# Buck_Boost_19V.net
KiCad netlist of a schematic drawn in Altium Designer
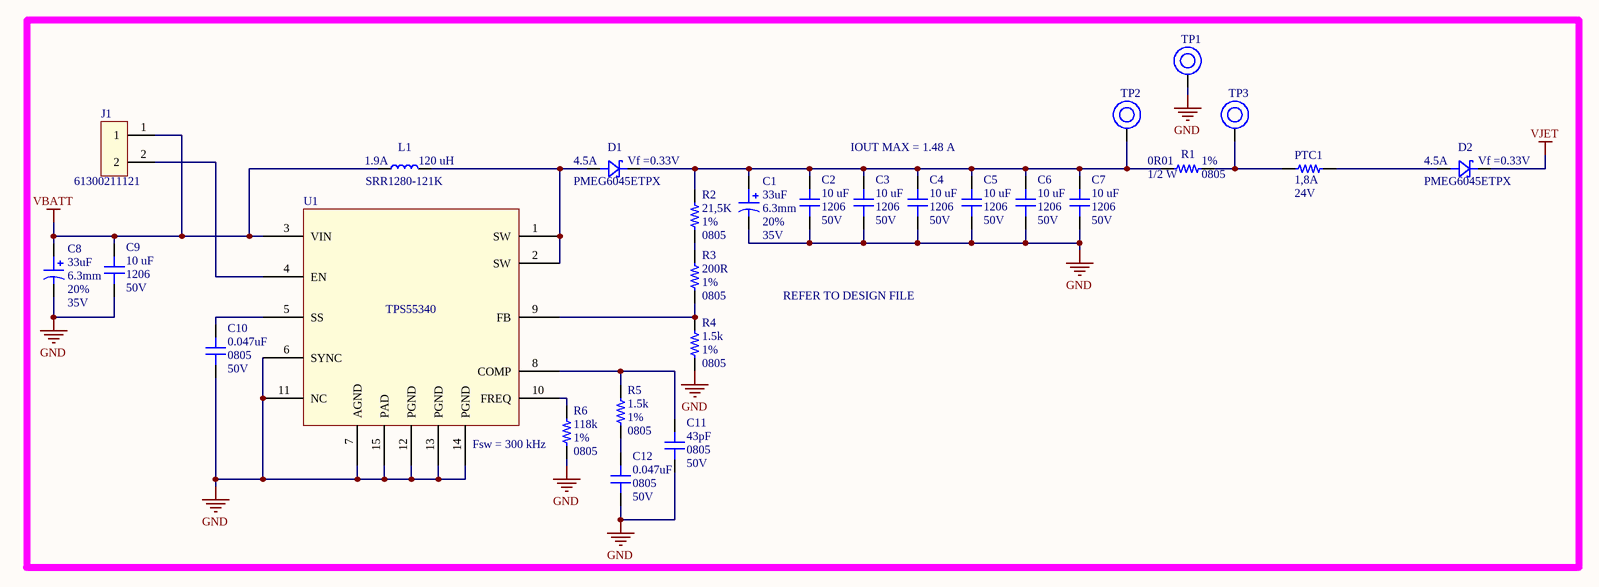
[diagram p0: Buck Boost 19V.SchDoc]

(export (version "E")
  (design (tool "Eeschema 10.0.6"))
  (components
    (comp (ref "C1")
      (value "33uF")
      (footprint "CAP ALU - 6.3mm DIA")
      (description "CAP ALU - 6.3mm")
      (fields
        (field (name "PACKAGE") "6.3mm")
        (field (name "TOLERANCE") "20%")
        (field (name "VOLTAGE") "35V")
        (field (name "PART NUMBER") "EEE-FK1V330P")
      )
      (libsource (lib "SecureBot") (part "CAP ALU - 6_3mm"))
    )
    (comp (ref "C2")
      (value "10 uF")
      (footprint "CAP_1206")
      (description "CAP - 1206")
      (fields
        (field (name "PACKAGE") "1206")
        (field (name "VOLTAGE") "50V")
        (field (name "PART NUMBER") "GRT31CR61H106ME01L")
      )
      (libsource (lib "SecureBot") (part "CAP - 1206"))
    )
    (comp (ref "C3")
      (value "10 uF")
      (footprint "CAP_1206")
      (description "CAP - 1206")
      (fields
        (field (name "PACKAGE") "1206")
        (field (name "VOLTAGE") "50V")
        (field (name "PART NUMBER") "GRT31CR61H106ME01L")
      )
      (libsource (lib "SecureBot") (part "CAP - 1206"))
    )
    (comp (ref "C4")
      (value "10 uF")
      (footprint "CAP_1206")
      (description "CAP - 1206")
      (fields
        (field (name "PACKAGE") "1206")
        (field (name "VOLTAGE") "50V")
        (field (name "PART NUMBER") "GRT31CR61H106ME01L")
      )
      (libsource (lib "SecureBot") (part "CAP - 1206"))
    )
    (comp (ref "C5")
      (value "10 uF")
      (footprint "CAP_1206")
      (description "CAP - 1206")
      (fields
        (field (name "PACKAGE") "1206")
        (field (name "VOLTAGE") "50V")
        (field (name "PART NUMBER") "GRT31CR61H106ME01L")
      )
      (libsource (lib "SecureBot") (part "CAP - 1206"))
    )
    (comp (ref "C6")
      (value "10 uF")
      (footprint "CAP_1206")
      (description "CAP - 1206")
      (fields
        (field (name "PACKAGE") "1206")
        (field (name "VOLTAGE") "50V")
        (field (name "PART NUMBER") "GRT31CR61H106ME01L")
      )
      (libsource (lib "SecureBot") (part "CAP - 1206"))
    )
    (comp (ref "C7")
      (value "10 uF")
      (footprint "CAP_1206")
      (description "CAP - 1206")
      (fields
        (field (name "PACKAGE") "1206")
        (field (name "VOLTAGE") "50V")
        (field (name "PART NUMBER") "GRT31CR61H106ME01L")
      )
      (libsource (lib "SecureBot") (part "CAP - 1206"))
    )
    (comp (ref "C8")
      (value "33uF")
      (footprint "CAP ALU - 6.3mm DIA")
      (description "CAP ALU - 6.3mm")
      (fields
        (field (name "PACKAGE") "6.3mm")
        (field (name "TOLERANCE") "20%")
        (field (name "VOLTAGE") "35V")
        (field (name "PART NUMBER") "EEE-FK1V330P")
      )
      (libsource (lib "SecureBot") (part "CAP ALU - 6_3mm"))
    )
    (comp (ref "C9")
      (value "10 uF")
      (footprint "CAP_1206")
      (description "CAP - 1206")
      (fields
        (field (name "PACKAGE") "1206")
        (field (name "VOLTAGE") "50V")
        (field (name "PART NUMBER") "GRT31CR61H106ME01L")
      )
      (libsource (lib "SecureBot") (part "CAP - 1206"))
    )
    (comp (ref "C10")
      (value "0.047uF")
      (footprint "CAP_0805")
      (description "CAP - 0805")
      (fields
        (field (name "PACKAGE") "0805")
        (field (name "VOLTAGE") "50V")
        (field (name "PART NUMBER") "C0805C473K5RACTU")
      )
      (libsource (lib "SecureBot") (part "CAP - 0805"))
    )
    (comp (ref "C11")
      (value "43pF")
      (footprint "CAP_0805")
      (description "CAP - 0805")
      (fields
        (field (name "PACKAGE") "0805")
        (field (name "VOLTAGE") "50V")
        (field (name "PART NUMBER") "C0805C430J5GAC7800")
      )
      (libsource (lib "SecureBot") (part "CAP - 0805"))
    )
    (comp (ref "C12")
      (value "0.047uF")
      (footprint "CAP_0805")
      (description "CAP - 0805")
      (fields
        (field (name "PACKAGE") "0805")
        (field (name "VOLTAGE") "50V")
        (field (name "PART NUMBER") "C0805C473K5RACTU")
      )
      (libsource (lib "SecureBot") (part "CAP - 0805"))
    )
    (comp (ref "D1")
      (value "SCHOTTKEY")
      (footprint "DO-214AC_SOD128")
      (fields
        (field (name "CURRENT") "4.5A")
        (field (name "VF") "Vf =0.33V")
        (field (name "PART NUMBER") "PMEG6045ETPX")
      )
      (libsource (lib "SecureBot") (part "SCHOTTKEY"))
    )
    (comp (ref "D2")
      (value "SCHOTTKEY")
      (footprint "DO-214AC_SOD128")
      (fields
        (field (name "CURRENT") "4.5A")
        (field (name "VF") "Vf =0.33V")
        (field (name "PART NUMBER") "PMEG6045ETPX")
      )
      (libsource (lib "SecureBot") (part "SCHOTTKEY"))
    )
    (comp (ref "J1")
      (value "Header 2 pin SM")
      (footprint "HDR1X2")
      (fields (field (name "PART NUMBER") "61300211121"))
      (libsource (lib "SecureBot") (part "Header 2 pin SM"))
    )
    (comp (ref "L1")
      (value "120 uH")
      (footprint "BOURNS 12.5x12.5mm")
      (description "IND")
      (fields (field (name "CURRENT") "1.9A") (field (name "PART NUMBER") "SRR1280-121K"))
      (libsource (lib "SecureBot") (part "IND"))
    )
    (comp (ref "PTC1")
      (value "PTC - 1812")
      (footprint "PTC - 1812")
      (fields
        (field (name "PART NUMBER") "0ZCG0110BF2B")
        (field (name "TRIP VALUE") "1,8A")
        (field (name "VOLTAGE") "24V")
      )
      (libsource (lib "SecureBot") (part "PTC - 1812"))
    )
    (comp (ref "R1")
      (value "0R01")
      (footprint "FER_0805")
      (description "RES - 0805")
      (fields
        (field (name "WATT") "1/2 W")
        (field (name "TOLERANCE") "1%")
        (field (name "PACKAGE") "0805")
        (field (name "PART NUMBER") "KRL1220E-M-R010-F-T5")
      )
      (libsource (lib "SecureBot") (part "RES - 0805"))
    )
    (comp (ref "R2")
      (value "21,5K")
      (footprint "FER_0805")
      (description "RES - 0805")
      (fields
        (field (name "TOLERANCE") "1%")
        (field (name "PACKAGE") "0805")
        (field (name "PART NUMBER") "ERJ-6ENF2152V")
      )
      (libsource (lib "SecureBot") (part "RES - 0805"))
    )
    (comp (ref "R3")
      (value "200R")
      (footprint "FER_0805")
      (description "RES - 0805")
      (fields
        (field (name "TOLERANCE") "1%")
        (field (name "PACKAGE") "0805")
        (field (name "PART NUMBER") "CRCW0805200RFKEA")
      )
      (libsource (lib "SecureBot") (part "RES - 0805"))
    )
    (comp (ref "R4")
      (value "1.5k")
      (footprint "FER_0805")
      (description "RES - 0805")
      (fields
        (field (name "TOLERANCE") "1%")
        (field (name "PACKAGE") "0805")
        (field (name "PART NUMBER") "CRCW08051K50FKEA")
      )
      (libsource (lib "SecureBot") (part "RES - 0805"))
    )
    (comp (ref "R5")
      (value "1.5k")
      (footprint "FER_0805")
      (description "RES - 0805")
      (fields
        (field (name "TOLERANCE") "1%")
        (field (name "PACKAGE") "0805")
        (field (name "PART NUMBER") "CRCW08051K50FKEA")
      )
      (libsource (lib "SecureBot") (part "RES - 0805"))
    )
    (comp (ref "R6")
      (value "118k")
      (footprint "FER_0805")
      (description "RES - 0805")
      (fields
        (field (name "TOLERANCE") "1%")
        (field (name "PACKAGE") "0805")
        (field (name "PART NUMBER") "CRCW0805118KFKEA")
      )
      (libsource (lib "SecureBot") (part "RES - 0805"))
    )
    (comp (ref "TP1")
      (value "TestPoint 3x3mm")
      (footprint "TestPoint 3X3mm")
      (libsource (lib "SecureBot") (part "TestPoint 3x3mm"))
    )
    (comp (ref "TP2")
      (value "TestPoint 3x3mm")
      (footprint "TestPoint 3X3mm")
      (libsource (lib "SecureBot") (part "TestPoint 3x3mm"))
    )
    (comp (ref "TP3")
      (value "TestPoint 3x3mm")
      (footprint "TestPoint 3X3mm")
      (libsource (lib "SecureBot") (part "TestPoint 3x3mm"))
    )
    (comp (ref "U1")
      (value "TPS55340")
      (footprint "14-TSSOP")
      (libsource (lib "SecureBot") (part "TPS55340"))
    )
  )
  (nets
    (net (code "1") (name "GND") (class "Default")
      (node (ref "C1") (pin "2") (pinfunction "2_2") (pintype "passive"))
      (node (ref "C10") (pin "2") (pinfunction "2_2") (pintype "passive"))
      (node (ref "C11") (pin "2") (pinfunction "2_2") (pintype "passive"))
      (node (ref "C12") (pin "2") (pinfunction "2_2") (pintype "passive"))
      (node (ref "C2") (pin "2") (pinfunction "2_2") (pintype "passive"))
      (node (ref "C3") (pin "2") (pinfunction "2_2") (pintype "passive"))
      (node (ref "C4") (pin "2") (pinfunction "2_2") (pintype "passive"))
      (node (ref "C5") (pin "2") (pinfunction "2_2") (pintype "passive"))
      (node (ref "C6") (pin "2") (pinfunction "2_2") (pintype "passive"))
      (node (ref "C7") (pin "2") (pinfunction "2_2") (pintype "passive"))
      (node (ref "C8") (pin "2") (pinfunction "2_2") (pintype "passive"))
      (node (ref "C9") (pin "2") (pinfunction "2_2") (pintype "passive"))
      (node (ref "R4") (pin "2") (pinfunction "2_2") (pintype "passive"))
      (node (ref "R6") (pin "2") (pinfunction "2_2") (pintype "passive"))
      (node (ref "TP1") (pin "1") (pinfunction "1_1") (pintype "passive"))
      (node (ref "U1") (pin "11") (pinfunction "NC_11") (pintype "passive"))
      (node (ref "U1") (pin "12") (pinfunction "PGND_12") (pintype "passive"))
      (node (ref "U1") (pin "13") (pinfunction "PGND_13") (pintype "passive"))
      (node (ref "U1") (pin "14") (pinfunction "PGND_14") (pintype "passive"))
      (node (ref "U1") (pin "15") (pinfunction "PAD_15") (pintype "passive"))
      (node (ref "U1") (pin "6") (pinfunction "SYNC_6") (pintype "passive"))
      (node (ref "U1") (pin "7") (pinfunction "AGND_7") (pintype "passive"))
    )
    (net (code "2") (name "Net-(C1-Pad1)") (class "Default")
      (node (ref "C1") (pin "1") (pinfunction "1_1") (pintype "passive"))
      (node (ref "C2") (pin "1") (pinfunction "1_1") (pintype "passive"))
      (node (ref "C3") (pin "1") (pinfunction "1_1") (pintype "passive"))
      (node (ref "C4") (pin "1") (pinfunction "1_1") (pintype "passive"))
      (node (ref "C5") (pin "1") (pinfunction "1_1") (pintype "passive"))
      (node (ref "C6") (pin "1") (pinfunction "1_1") (pintype "passive"))
      (node (ref "C7") (pin "1") (pinfunction "1_1") (pintype "passive"))
      (node (ref "D1") (pin "2") (pinfunction "2_2") (pintype "passive"))
      (node (ref "R1") (pin "1") (pinfunction "1_1") (pintype "passive"))
      (node (ref "R2") (pin "1") (pinfunction "1_1") (pintype "passive"))
      (node (ref "TP2") (pin "1") (pinfunction "1_1") (pintype "passive"))
    )
    (net (code "3") (name "Net-(C12-Pad1)") (class "Default")
      (node (ref "C12") (pin "1") (pinfunction "1_1") (pintype "passive"))
      (node (ref "R5") (pin "2") (pinfunction "2_2") (pintype "passive"))
    )
    (net (code "4") (name "Net-(D1-Pad1)") (class "Default")
      (node (ref "D1") (pin "1") (pinfunction "1_1") (pintype "passive"))
      (node (ref "L1") (pin "2") (pinfunction "2_2") (pintype "passive"))
      (node (ref "U1") (pin "1") (pinfunction "SW_1") (pintype "passive"))
      (node (ref "U1") (pin "2") (pinfunction "SW_2") (pintype "passive"))
    )
    (net (code "5") (name "Net-(D2-Pad1)") (class "Default")
      (node (ref "D2") (pin "1") (pinfunction "1_1") (pintype "passive"))
      (node (ref "PTC1") (pin "2") (pinfunction "2_2") (pintype "passive"))
    )
    (net (code "6") (name "Net-(PTC1-Pad1)") (class "Default")
      (node (ref "PTC1") (pin "1") (pinfunction "1_1") (pintype "passive"))
      (node (ref "R1") (pin "2") (pinfunction "2_2") (pintype "passive"))
      (node (ref "TP3") (pin "1") (pinfunction "1_1") (pintype "passive"))
    )
    (net (code "7") (name "Net-(R2-Pad2)") (class "Default")
      (node (ref "R2") (pin "2") (pinfunction "2_2") (pintype "passive"))
      (node (ref "R3") (pin "1") (pinfunction "1_1") (pintype "passive"))
    )
    (net (code "8") (name "Net-(U1-COMP)") (class "Default")
      (node (ref "C11") (pin "1") (pinfunction "1_1") (pintype "passive"))
      (node (ref "R5") (pin "1") (pinfunction "1_1") (pintype "passive"))
      (node (ref "U1") (pin "8") (pinfunction "COMP_8") (pintype "passive"))
    )
    (net (code "9") (name "Net-(U1-EN)") (class "Default")
      (node (ref "J1") (pin "2") (pinfunction "2_2") (pintype "passive"))
      (node (ref "U1") (pin "4") (pinfunction "EN_4") (pintype "passive"))
    )
    (net (code "10") (name "Net-(U1-FB)") (class "Default")
      (node (ref "R3") (pin "2") (pinfunction "2_2") (pintype "passive"))
      (node (ref "R4") (pin "1") (pinfunction "1_1") (pintype "passive"))
      (node (ref "U1") (pin "9") (pinfunction "FB_9") (pintype "passive"))
    )
    (net (code "11") (name "Net-(U1-FREQ)") (class "Default")
      (node (ref "R6") (pin "1") (pinfunction "1_1") (pintype "passive"))
      (node (ref "U1") (pin "10") (pinfunction "FREQ_10") (pintype "passive"))
    )
    (net (code "12") (name "Net-(U1-SS)") (class "Default")
      (node (ref "C10") (pin "1") (pinfunction "1_1") (pintype "passive"))
      (node (ref "U1") (pin "5") (pinfunction "SS_5") (pintype "passive"))
    )
    (net (code "13") (name "VBATT") (class "Default")
      (node (ref "C8") (pin "1") (pinfunction "1_1") (pintype "passive"))
      (node (ref "C9") (pin "1") (pinfunction "1_1") (pintype "passive"))
      (node (ref "J1") (pin "1") (pinfunction "1_1") (pintype "passive"))
      (node (ref "L1") (pin "1") (pinfunction "1_1") (pintype "passive"))
      (node (ref "U1") (pin "3") (pinfunction "VIN_3") (pintype "passive"))
    )
    (net (code "14") (name "VJET") (class "Default")
      (node (ref "D2") (pin "2") (pinfunction "2_2") (pintype "passive"))
    )
  )
)
